# ESP8266_MegaD_adapter_board_v0_1.net
KiCad netlist of a schematic drawn in EAGLE
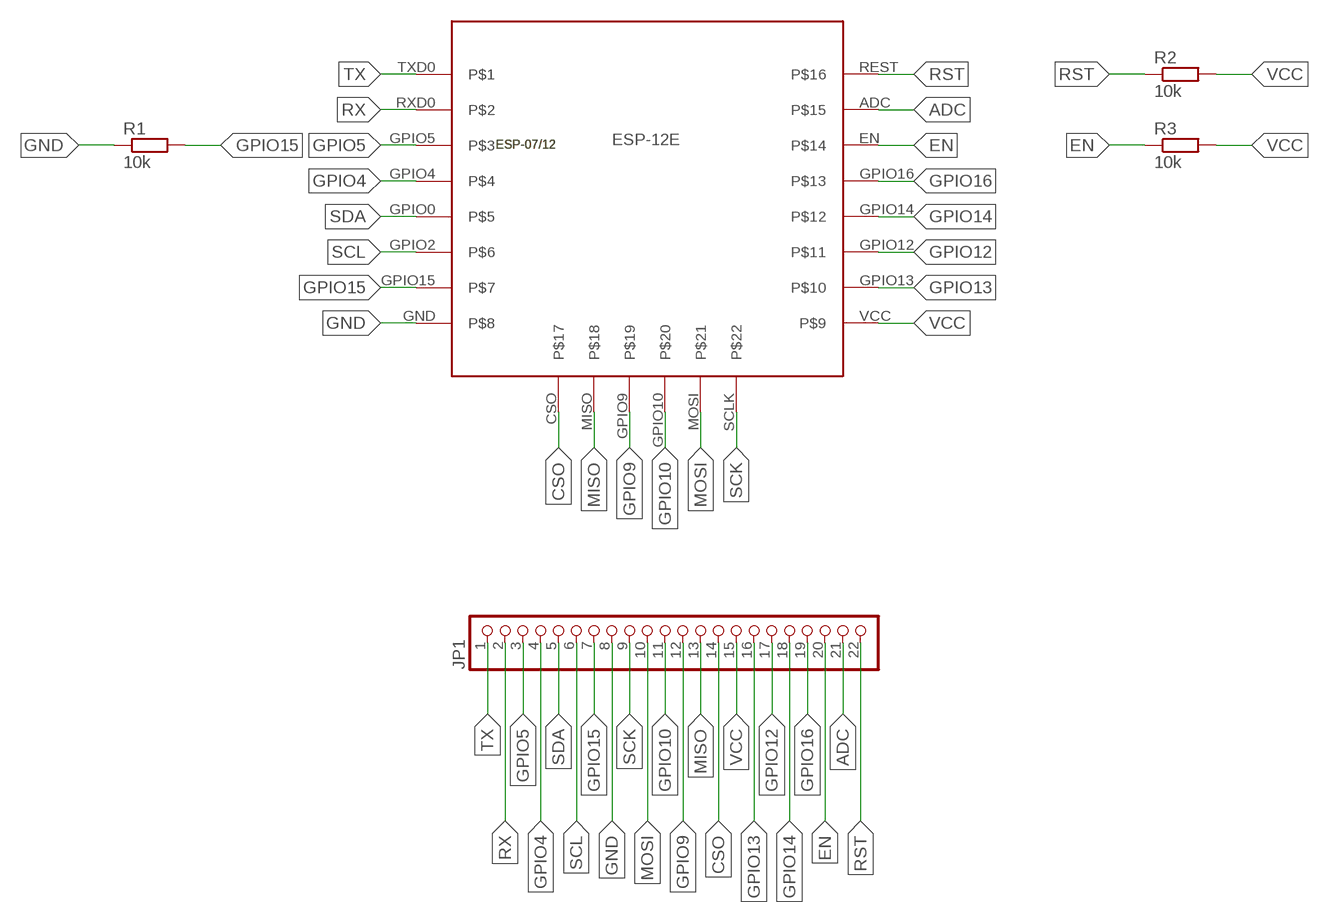
[diagram p0: schematic, sheet 1]

(export (version "E")
  (design (tool "Eeschema 10.0.6"))
  (components
    (comp (ref "JP1")
      (value "PINHD-1X22")
      (footprint "eagle-import:1X22")
      (libsource (lib "eagle-import") (part "PINHD-1X22"))
    )
    (comp (ref "R1")
      (value "10k")
      (footprint "eagle-import:R1206")
      (libsource (lib "eagle-import") (part "R-EU_R1206"))
    )
    (comp (ref "R2")
      (value "10k")
      (footprint "eagle-import:R1206")
      (libsource (lib "eagle-import") (part "R-EU_R1206"))
    )
    (comp (ref "R3")
      (value "10k")
      (footprint "eagle-import:R1206")
      (libsource (lib "eagle-import") (part "R-EU_R1206"))
    )
    (comp (ref "U$3")
      (value "ESP-07/12_ESP-12E")
      (footprint "eagle-import:ESP-07_12")
      (libsource (lib "eagle-import") (part "ESP-07/12_ESP-12E"))
    )
  )
  (nets
    (net (code "1") (name "ADC") (class "Default")
      (node (ref "JP1") (pin "21") (pinfunction "21_21") (pintype "passive"))
      (node (ref "U$3") (pin "ADC") (pinfunction "P$15_ADC") (pintype "bidirectional"))
    )
    (net (code "2") (name "CSO") (class "Default")
      (node (ref "JP1") (pin "14") (pinfunction "14_14") (pintype "passive"))
      (node (ref "U$3") (pin "CSO") (pinfunction "P$17_CSO") (pintype "bidirectional"))
    )
    (net (code "3") (name "EN") (class "Default")
      (node (ref "JP1") (pin "20") (pinfunction "20_20") (pintype "passive"))
      (node (ref "R3") (pin "1") (pinfunction "1_1") (pintype "passive"))
      (node (ref "U$3") (pin "EN") (pinfunction "P$14_EN") (pintype "bidirectional"))
    )
    (net (code "4") (name "GND") (class "Default")
      (node (ref "JP1") (pin "8") (pinfunction "8_8") (pintype "passive"))
      (node (ref "R1") (pin "1") (pinfunction "1_1") (pintype "passive"))
      (node (ref "U$3") (pin "GND") (pinfunction "P$8_GND") (pintype "bidirectional"))
    )
    (net (code "5") (name "GPIO4") (class "Default")
      (node (ref "JP1") (pin "4") (pinfunction "4_4") (pintype "passive"))
      (node (ref "U$3") (pin "GPIO4") (pinfunction "P$4_GPIO4") (pintype "bidirectional"))
    )
    (net (code "6") (name "GPIO5") (class "Default")
      (node (ref "JP1") (pin "3") (pinfunction "3_3") (pintype "passive"))
      (node (ref "U$3") (pin "GPIO5") (pinfunction "P$3_GPIO5") (pintype "bidirectional"))
    )
    (net (code "7") (name "GPIO9") (class "Default")
      (node (ref "JP1") (pin "12") (pinfunction "12_12") (pintype "passive"))
      (node (ref "U$3") (pin "GPIO9") (pinfunction "P$19_GPIO9") (pintype "bidirectional"))
    )
    (net (code "8") (name "GPIO10") (class "Default")
      (node (ref "JP1") (pin "11") (pinfunction "11_11") (pintype "passive"))
      (node (ref "U$3") (pin "GPIO10") (pinfunction "P$20_GPIO10") (pintype "bidirectional"))
    )
    (net (code "9") (name "GPIO12") (class "Default")
      (node (ref "JP1") (pin "17") (pinfunction "17_17") (pintype "passive"))
      (node (ref "U$3") (pin "GPIO12") (pinfunction "P$11_GPIO12") (pintype "bidirectional"))
    )
    (net (code "10") (name "GPIO13") (class "Default")
      (node (ref "JP1") (pin "16") (pinfunction "16_16") (pintype "passive"))
      (node (ref "U$3") (pin "GPIO13") (pinfunction "P$10_GPIO13") (pintype "bidirectional"))
    )
    (net (code "11") (name "GPIO14") (class "Default")
      (node (ref "JP1") (pin "18") (pinfunction "18_18") (pintype "passive"))
      (node (ref "U$3") (pin "GPIO14") (pinfunction "P$12_GPIO14") (pintype "bidirectional"))
    )
    (net (code "12") (name "GPIO15") (class "Default")
      (node (ref "JP1") (pin "7") (pinfunction "7_7") (pintype "passive"))
      (node (ref "R1") (pin "2") (pinfunction "2_2") (pintype "passive"))
      (node (ref "U$3") (pin "GPIO15") (pinfunction "P$7_GPIO15") (pintype "bidirectional"))
    )
    (net (code "13") (name "GPIO16") (class "Default")
      (node (ref "JP1") (pin "19") (pinfunction "19_19") (pintype "passive"))
      (node (ref "U$3") (pin "GPIO16") (pinfunction "P$13_GPIO16") (pintype "bidirectional"))
    )
    (net (code "14") (name "MISO") (class "Default")
      (node (ref "JP1") (pin "13") (pinfunction "13_13") (pintype "passive"))
      (node (ref "U$3") (pin "MISO") (pinfunction "P$18_MISO") (pintype "bidirectional"))
    )
    (net (code "15") (name "MOSI") (class "Default")
      (node (ref "JP1") (pin "10") (pinfunction "10_10") (pintype "passive"))
      (node (ref "U$3") (pin "MOSI") (pinfunction "P$21_MOSI") (pintype "bidirectional"))
    )
    (net (code "16") (name "RST") (class "Default")
      (node (ref "JP1") (pin "22") (pinfunction "22_22") (pintype "passive"))
      (node (ref "R2") (pin "1") (pinfunction "1_1") (pintype "passive"))
      (node (ref "U$3") (pin "REST") (pinfunction "P$16_REST") (pintype "bidirectional"))
    )
    (net (code "17") (name "RX") (class "Default")
      (node (ref "JP1") (pin "2") (pinfunction "2_2") (pintype "passive"))
      (node (ref "U$3") (pin "RXD0") (pinfunction "P$2_RXD0") (pintype "bidirectional"))
    )
    (net (code "18") (name "SCK") (class "Default")
      (node (ref "JP1") (pin "9") (pinfunction "9_9") (pintype "passive"))
      (node (ref "U$3") (pin "SCLK") (pinfunction "P$22_SCLK") (pintype "bidirectional"))
    )
    (net (code "19") (name "SCL") (class "Default")
      (node (ref "JP1") (pin "6") (pinfunction "6_6") (pintype "passive"))
      (node (ref "U$3") (pin "GPIO2") (pinfunction "P$6_GPIO2") (pintype "bidirectional"))
    )
    (net (code "20") (name "SDA") (class "Default")
      (node (ref "JP1") (pin "5") (pinfunction "5_5") (pintype "passive"))
      (node (ref "U$3") (pin "GPIO0") (pinfunction "P$5_GPIO0") (pintype "bidirectional"))
    )
    (net (code "21") (name "TX") (class "Default")
      (node (ref "JP1") (pin "1") (pinfunction "1_1") (pintype "passive"))
      (node (ref "U$3") (pin "TXD0") (pinfunction "P$1_TXD0") (pintype "bidirectional"))
    )
    (net (code "22") (name "VCC") (class "Default")
      (node (ref "JP1") (pin "15") (pinfunction "15_15") (pintype "passive"))
      (node (ref "R2") (pin "2") (pinfunction "2_2") (pintype "passive"))
      (node (ref "R3") (pin "2") (pinfunction "2_2") (pintype "passive"))
      (node (ref "U$3") (pin "VCC") (pinfunction "P$9_VCC") (pintype "bidirectional"))
    )
  )
)
